# RocketDuino.net
KiCad netlist of a schematic drawn in EAGLE
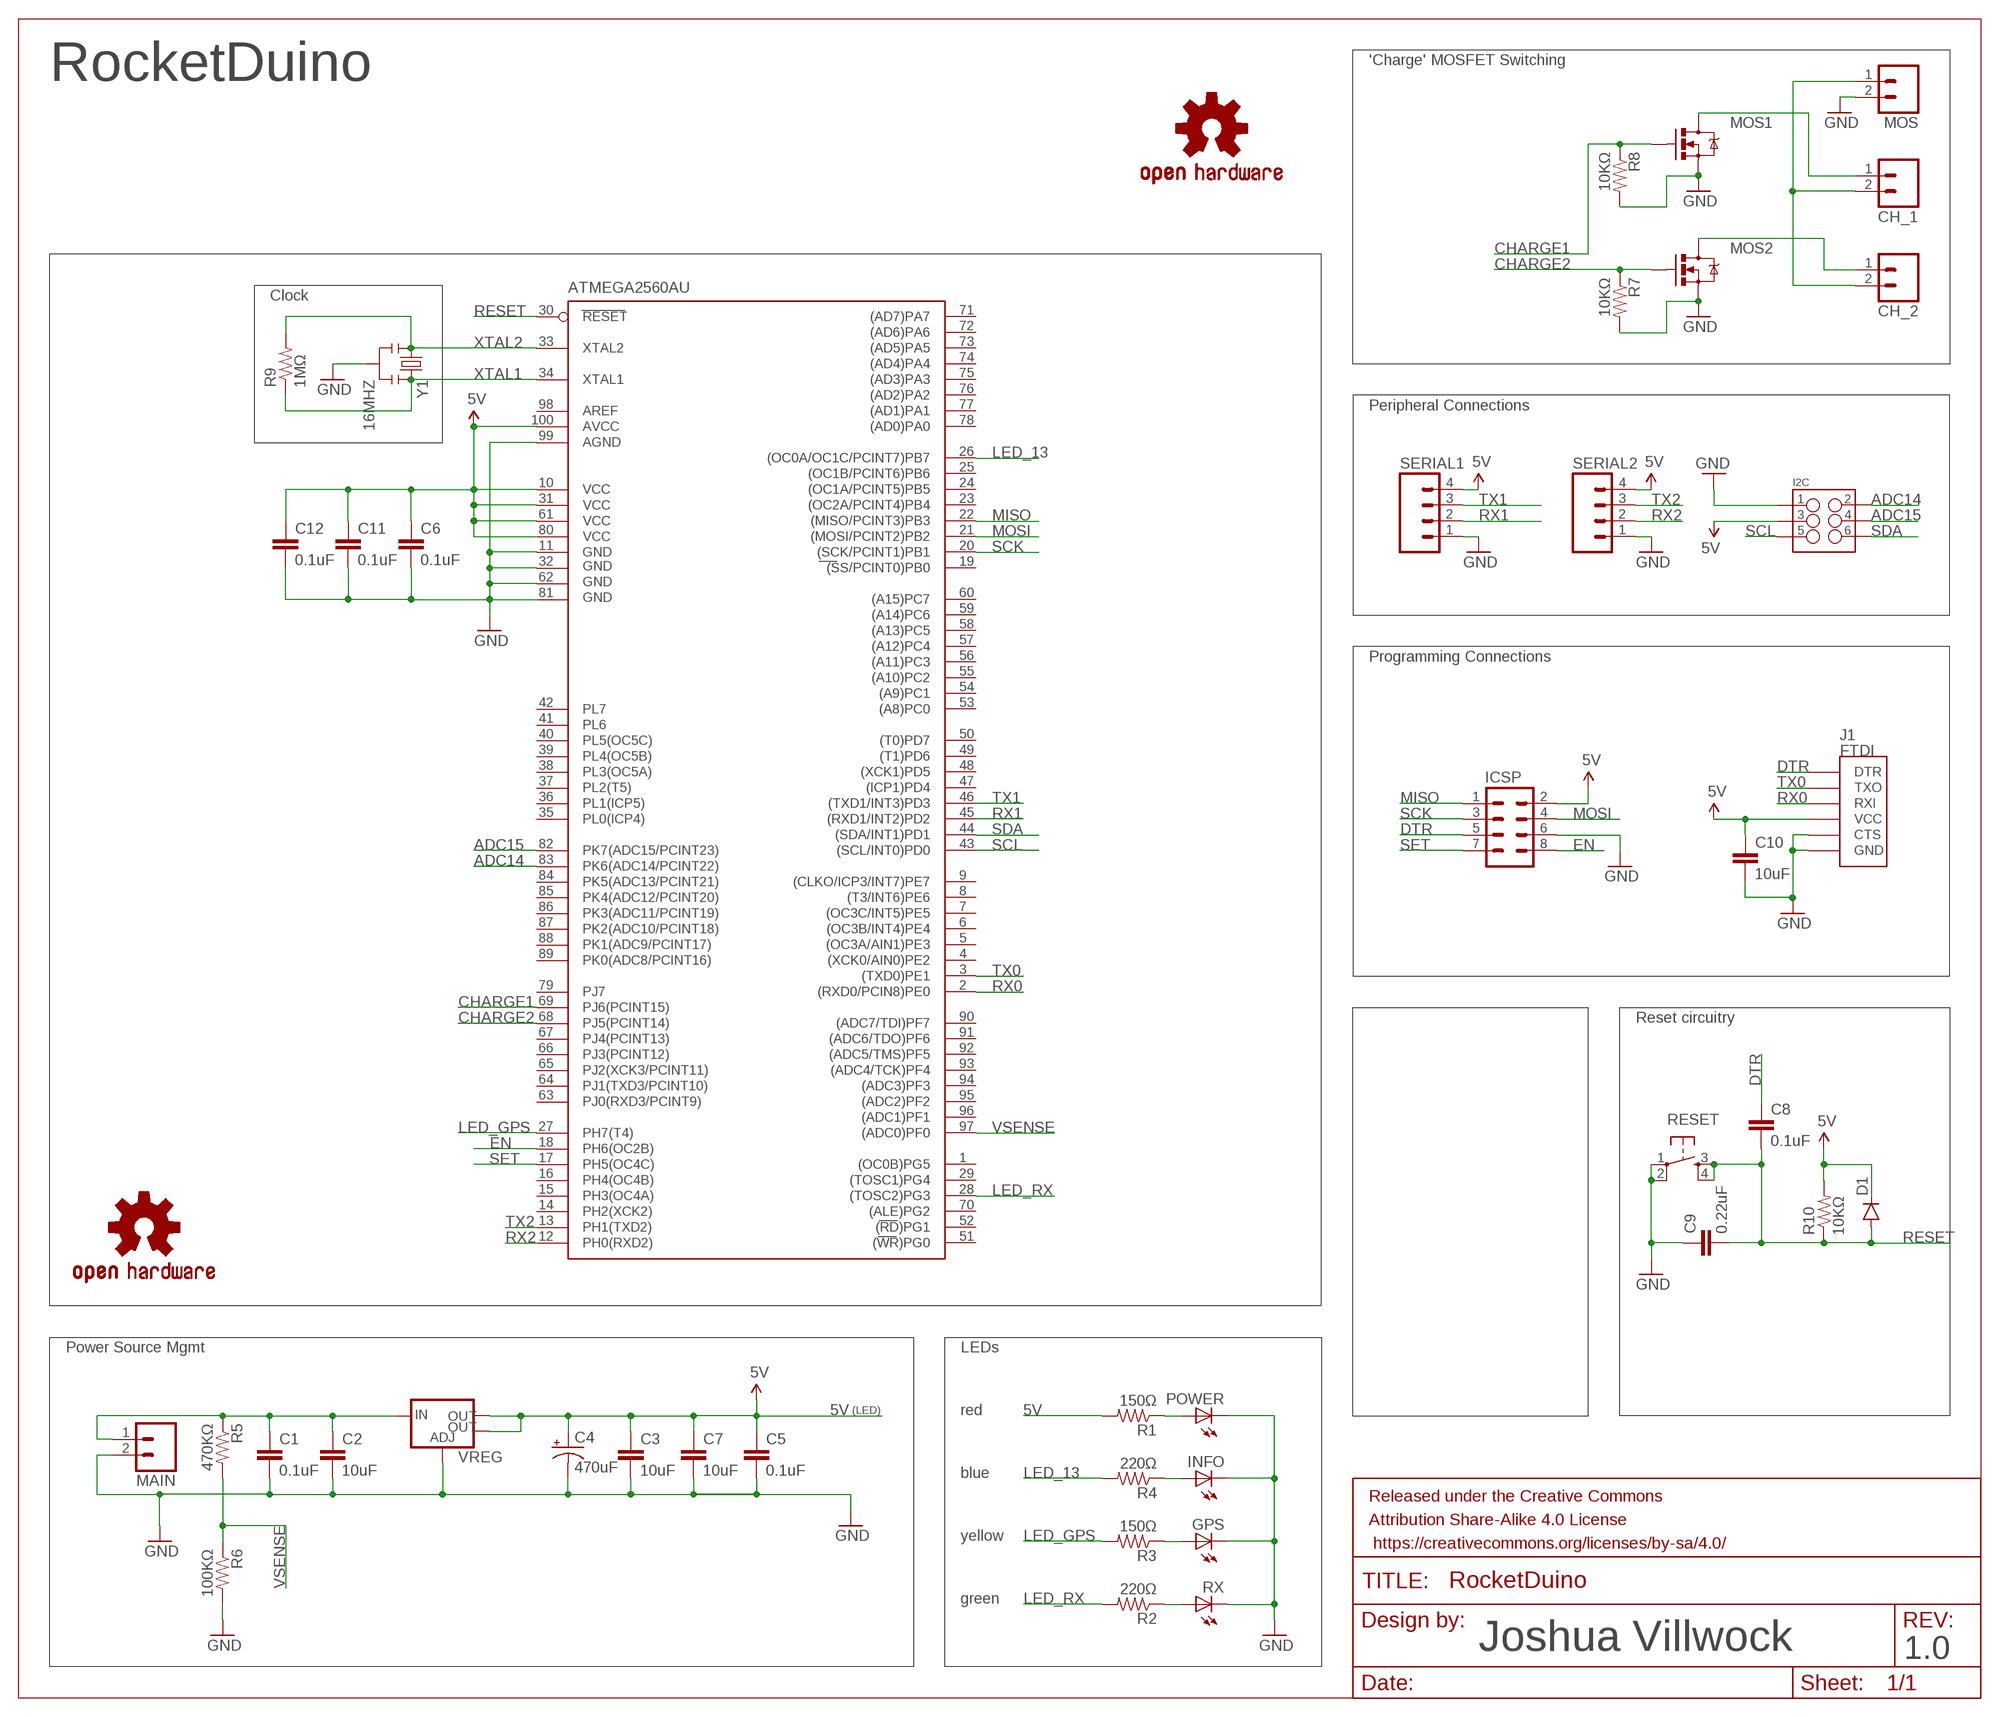
[diagram p0: schematic, sheet 1]

(export (version "E")
  (design (tool "Eeschema 10.0.6"))
  (components
    (comp (ref "ATMEGA2560AU")
      (value "ATMEGA2560AU")
      (footprint "eagle-import:TQFP100")
      (libsource (lib "eagle-import") (part "ATMEGA2560AU"))
    )
    (comp (ref "C1")
      (value "0.1uF")
      (footprint "eagle-import:1206")
      (libsource (lib "eagle-import") (part "CAP1206"))
    )
    (comp (ref "C2")
      (value "10uF")
      (footprint "eagle-import:1206")
      (libsource (lib "eagle-import") (part "CAP1206"))
    )
    (comp (ref "C3")
      (value "10uF")
      (footprint "eagle-import:1206")
      (libsource (lib "eagle-import") (part "CAP1206"))
    )
    (comp (ref "C4")
      (value "470uF")
      (footprint "eagle-import:CPOL-RADIAL-100UF-25V")
      (libsource (lib "eagle-import") (part "CAP_POLPTH1"))
    )
    (comp (ref "C5")
      (value "0.1uF")
      (footprint "eagle-import:1206")
      (libsource (lib "eagle-import") (part "CAP1206"))
    )
    (comp (ref "C6")
      (value "0.1uF")
      (footprint "eagle-import:1206")
      (libsource (lib "eagle-import") (part "CAP1206"))
    )
    (comp (ref "C7")
      (value "10uF")
      (footprint "eagle-import:1206")
      (libsource (lib "eagle-import") (part "CAP1206"))
    )
    (comp (ref "C8")
      (value "0.1uF")
      (footprint "eagle-import:1206")
      (libsource (lib "eagle-import") (part "CAP1206"))
    )
    (comp (ref "C9")
      (value "0.22uF")
      (footprint "eagle-import:1206")
      (libsource (lib "eagle-import") (part "CAP1206"))
    )
    (comp (ref "C10")
      (value "10uF")
      (footprint "eagle-import:1206")
      (libsource (lib "eagle-import") (part "CAP1206"))
    )
    (comp (ref "C11")
      (value "0.1uF")
      (footprint "eagle-import:1206")
      (libsource (lib "eagle-import") (part "CAP1206"))
    )
    (comp (ref "C12")
      (value "0.1uF")
      (footprint "eagle-import:1206")
      (libsource (lib "eagle-import") (part "CAP1206"))
    )
    (comp (ref "CH_1")
      (value "M02LOCK_LONGPADS")
      (footprint "eagle-import:1X02_LOCK_LONGPADS")
      (libsource (lib "eagle-import") (part "M02LOCK_LONGPADS"))
    )
    (comp (ref "CH_2")
      (value "M02LOCK_LONGPADS")
      (footprint "eagle-import:1X02_LOCK_LONGPADS")
      (libsource (lib "eagle-import") (part "M02LOCK_LONGPADS"))
    )
    (comp (ref "D1")
      (value "DIODESMA-ALT")
      (footprint "eagle-import:SMA-DIODE_ALT")
      (libsource (lib "eagle-import") (part "DIODESMA-ALT"))
    )
    (comp (ref "FRAME1")
      (value "FRAME-LEDGER")
      (footprint "eagle-import:CREATIVE_COMMONS")
      (libsource (lib "eagle-import") (part "FRAME-LEDGER"))
    )
    (comp (ref "GPS")
      (value "LEDSML0805")
      (footprint "eagle-import:SML0805")
      (libsource (lib "eagle-import") (part "LEDSML0805"))
    )
    (comp (ref "I2C")
      (value "M03X2FEMALE")
      (footprint "eagle-import:2X3")
      (libsource (lib "eagle-import") (part "M03X2FEMALE"))
    )
    (comp (ref "ICSP")
      (value "M04X2")
      (footprint "eagle-import:2X4")
      (libsource (lib "eagle-import") (part "M04X2"))
    )
    (comp (ref "INFO")
      (value "LEDSML0805")
      (footprint "eagle-import:SML0805")
      (libsource (lib "eagle-import") (part "LEDSML0805"))
    )
    (comp (ref "J1")
      (value "FTDI")
      (footprint "eagle-import:FTDI_DEVICE_SIDE")
      (libsource (lib "eagle-import") (part "FTDI_DEVICE"))
    )
    (comp (ref "LOGO1")
      (value "OSHW-LOGOM")
      (footprint "eagle-import:OSHW-LOGO-M")
      (libsource (lib "eagle-import") (part "OSHW-LOGOM"))
    )
    (comp (ref "LOGO2")
      (value "OSHW-LOGOM")
      (footprint "eagle-import:OSHW-LOGO-M")
      (libsource (lib "eagle-import") (part "OSHW-LOGOM"))
    )
    (comp (ref "MAIN")
      (value "M02LOCK_LONGPADS")
      (footprint "eagle-import:1X02_LOCK_LONGPADS")
      (libsource (lib "eagle-import") (part "M02LOCK_LONGPADS"))
    )
    (comp (ref "MOS")
      (value "M02LOCK_LONGPADS")
      (footprint "eagle-import:1X02_LOCK_LONGPADS")
      (libsource (lib "eagle-import") (part "M02LOCK_LONGPADS"))
    )
    (comp (ref "MOS1")
      (value "MOSFET-NCHANNELFQP30N06L")
      (footprint "eagle-import:TO220V")
      (libsource (lib "eagle-import") (part "MOSFET-NCHANNELFQP30N06L"))
    )
    (comp (ref "MOS2")
      (value "MOSFET-NCHANNELFQP30N06L")
      (footprint "eagle-import:TO220V")
      (libsource (lib "eagle-import") (part "MOSFET-NCHANNELFQP30N06L"))
    )
    (comp (ref "POWER")
      (value "LEDSML0805")
      (footprint "eagle-import:SML0805")
      (libsource (lib "eagle-import") (part "LEDSML0805"))
    )
    (comp (ref "R1")
      (value "150Ω")
      (footprint "eagle-import:1206")
      (libsource (lib "eagle-import") (part "RESISTOR1206"))
    )
    (comp (ref "R2")
      (value "220Ω")
      (footprint "eagle-import:1206")
      (libsource (lib "eagle-import") (part "RESISTOR1206"))
    )
    (comp (ref "R3")
      (value "150Ω")
      (footprint "eagle-import:1206")
      (libsource (lib "eagle-import") (part "RESISTOR1206"))
    )
    (comp (ref "R4")
      (value "220Ω")
      (footprint "eagle-import:1206")
      (libsource (lib "eagle-import") (part "RESISTOR1206"))
    )
    (comp (ref "R5")
      (value "470KΩ")
      (footprint "eagle-import:1206")
      (libsource (lib "eagle-import") (part "RESISTOR1206"))
    )
    (comp (ref "R6")
      (value "100KΩ")
      (footprint "eagle-import:1206")
      (libsource (lib "eagle-import") (part "RESISTOR1206"))
    )
    (comp (ref "R7")
      (value "10KΩ")
      (footprint "eagle-import:1206")
      (libsource (lib "eagle-import") (part "RESISTOR1206"))
    )
    (comp (ref "R8")
      (value "10KΩ")
      (footprint "eagle-import:1206")
      (libsource (lib "eagle-import") (part "RESISTOR1206"))
    )
    (comp (ref "R9")
      (value "1MΩ")
      (footprint "eagle-import:1206")
      (libsource (lib "eagle-import") (part "RESISTOR1206"))
    )
    (comp (ref "R10")
      (value "10KΩ")
      (footprint "eagle-import:1206")
      (libsource (lib "eagle-import") (part "RESISTOR1206"))
    )
    (comp (ref "RESET")
      (value "SWITCH_SPST_4_PINSQUARE")
      (footprint "eagle-import:TACTILE-SWITCH-SMD")
      (libsource (lib "eagle-import") (part "SWITCH_SPST_4_PINSQUARE"))
    )
    (comp (ref "RX")
      (value "LEDSML0805")
      (footprint "eagle-import:SML0805")
      (libsource (lib "eagle-import") (part "LEDSML0805"))
    )
    (comp (ref "SERIAL1")
      (value "M04POLAR")
      (footprint "eagle-import:MOLEX-1X4")
      (libsource (lib "eagle-import") (part "M04POLAR"))
    )
    (comp (ref "SERIAL2")
      (value "M04POLAR")
      (footprint "eagle-import:MOLEX-1X4")
      (libsource (lib "eagle-import") (part "M04POLAR"))
    )
    (comp (ref "VREG")
      (value "V_REG_LM1117SOT223")
      (footprint "eagle-import:SOT223")
      (libsource (lib "eagle-import") (part "V_REG_LM1117SOT223"))
    )
    (comp (ref "Y1")
      (value "16MHZ")
      (footprint "eagle-import:RESONATOR-SMD")
      (libsource (lib "eagle-import") (part "RESONATOR16MHZ"))
    )
  )
  (nets
    (net (code "1") (name "/ADC14") (class "Default")
      (node (ref "ATMEGA2560AU") (pin "83") (pinfunction "PK6(ADC14/PCINT22)_83") (pintype "bidirectional"))
      (node (ref "I2C") (pin "2") (pinfunction "2_2") (pintype "bidirectional"))
    )
    (net (code "2") (name "/ADC15") (class "Default")
      (node (ref "ATMEGA2560AU") (pin "82") (pinfunction "PK7(ADC15/PCINT23)_82") (pintype "bidirectional"))
      (node (ref "I2C") (pin "4") (pinfunction "4_4") (pintype "bidirectional"))
    )
    (net (code "3") (name "/CHARGE1") (class "Default")
      (node (ref "ATMEGA2560AU") (pin "69") (pinfunction "PJ6(PCINT15)_69") (pintype "bidirectional"))
      (node (ref "MOS1") (pin "1") (pinfunction "G_1") (pintype "passive"))
      (node (ref "R8") (pin "1") (pinfunction "1_1") (pintype "passive"))
    )
    (net (code "4") (name "/CHARGE2") (class "Default")
      (node (ref "ATMEGA2560AU") (pin "68") (pinfunction "PJ5(PCINT14)_68") (pintype "bidirectional"))
      (node (ref "MOS2") (pin "1") (pinfunction "G_1") (pintype "passive"))
      (node (ref "R7") (pin "1") (pinfunction "1_1") (pintype "passive"))
    )
    (net (code "5") (name "/DTR") (class "Default")
      (node (ref "C8") (pin "1") (pinfunction "1_1") (pintype "passive"))
      (node (ref "ICSP") (pin "5") (pinfunction "5_5") (pintype "passive"))
      (node (ref "J1") (pin "P$1") (pinfunction "DTR_P$1") (pintype "bidirectional"))
    )
    (net (code "6") (name "/EN") (class "Default")
      (node (ref "ATMEGA2560AU") (pin "18") (pinfunction "PH6(OC2B)_18") (pintype "bidirectional"))
      (node (ref "ICSP") (pin "8") (pinfunction "8_8") (pintype "passive"))
    )
    (net (code "7") (name "/LED_13") (class "Default")
      (node (ref "ATMEGA2560AU") (pin "26") (pinfunction "(OC0A/OC1C/PCINT7)PB7_26") (pintype "bidirectional"))
      (node (ref "R4") (pin "2") (pinfunction "2_2") (pintype "passive"))
    )
    (net (code "8") (name "/LED_GPS") (class "Default")
      (node (ref "ATMEGA2560AU") (pin "27") (pinfunction "PH7(T4)_27") (pintype "bidirectional"))
      (node (ref "R3") (pin "2") (pinfunction "2_2") (pintype "passive"))
    )
    (net (code "9") (name "/LED_RX") (class "Default")
      (node (ref "ATMEGA2560AU") (pin "28") (pinfunction "(TOSC2)PG3_28") (pintype "bidirectional"))
      (node (ref "R2") (pin "2") (pinfunction "2_2") (pintype "passive"))
    )
    (net (code "10") (name "/MISO") (class "Default")
      (node (ref "ATMEGA2560AU") (pin "22") (pinfunction "(MISO/PCINT3)PB3_22") (pintype "bidirectional"))
      (node (ref "ICSP") (pin "1") (pinfunction "1_1") (pintype "passive"))
    )
    (net (code "11") (name "/MOSI") (class "Default")
      (node (ref "ATMEGA2560AU") (pin "21") (pinfunction "(MOSI/PCINT2)PB2_21") (pintype "bidirectional"))
      (node (ref "ICSP") (pin "4") (pinfunction "4_4") (pintype "passive"))
    )
    (net (code "12") (name "/RESET") (class "Default")
      (node (ref "ATMEGA2560AU") (pin "30") (pinfunction "RESET_30") (pintype "input"))
      (node (ref "C8") (pin "2") (pinfunction "2_2") (pintype "passive"))
      (node (ref "C9") (pin "2") (pinfunction "2_2") (pintype "passive"))
      (node (ref "D1") (pin "A") (pinfunction "A_A") (pintype "passive"))
      (node (ref "R10") (pin "1") (pinfunction "1_1") (pintype "passive"))
      (node (ref "RESET") (pin "3") (pinfunction "3_3") (pintype "passive"))
      (node (ref "RESET") (pin "4") (pinfunction "4_4") (pintype "passive"))
    )
    (net (code "13") (name "/RX0") (class "Default")
      (node (ref "ATMEGA2560AU") (pin "2") (pinfunction "(RXD0/PCIN8)PE0_2") (pintype "bidirectional"))
      (node (ref "J1") (pin "P$3") (pinfunction "RXI_P$3") (pintype "bidirectional"))
    )
    (net (code "14") (name "/RX1") (class "Default")
      (node (ref "ATMEGA2560AU") (pin "45") (pinfunction "(RXD1/INT2)PD2_45") (pintype "bidirectional"))
      (node (ref "SERIAL1") (pin "2") (pinfunction "2_2") (pintype "passive"))
    )
    (net (code "15") (name "/RX2") (class "Default")
      (node (ref "ATMEGA2560AU") (pin "12") (pinfunction "PH0(RXD2)_12") (pintype "bidirectional"))
      (node (ref "SERIAL2") (pin "2") (pinfunction "2_2") (pintype "passive"))
    )
    (net (code "16") (name "/SCK") (class "Default")
      (node (ref "ATMEGA2560AU") (pin "20") (pinfunction "(SCK/PCINT1)PB1_20") (pintype "bidirectional"))
      (node (ref "ICSP") (pin "3") (pinfunction "3_3") (pintype "passive"))
    )
    (net (code "17") (name "/SCL") (class "Default")
      (node (ref "ATMEGA2560AU") (pin "43") (pinfunction "(SCL/INT0)PD0_43") (pintype "bidirectional"))
      (node (ref "I2C") (pin "5") (pinfunction "5_5") (pintype "bidirectional"))
    )
    (net (code "18") (name "/SDA") (class "Default")
      (node (ref "ATMEGA2560AU") (pin "44") (pinfunction "(SDA/INT1)PD1_44") (pintype "bidirectional"))
      (node (ref "I2C") (pin "6") (pinfunction "6_6") (pintype "bidirectional"))
    )
    (net (code "19") (name "/SET") (class "Default")
      (node (ref "ATMEGA2560AU") (pin "17") (pinfunction "PH5(OC4C)_17") (pintype "bidirectional"))
      (node (ref "ICSP") (pin "7") (pinfunction "7_7") (pintype "passive"))
    )
    (net (code "20") (name "/TX0") (class "Default")
      (node (ref "ATMEGA2560AU") (pin "3") (pinfunction "(TXD0)PE1_3") (pintype "bidirectional"))
      (node (ref "J1") (pin "P$2") (pinfunction "TXO_P$2") (pintype "bidirectional"))
    )
    (net (code "21") (name "/TX1") (class "Default")
      (node (ref "ATMEGA2560AU") (pin "46") (pinfunction "(TXD1/INT3)PD3_46") (pintype "bidirectional"))
      (node (ref "SERIAL1") (pin "3") (pinfunction "3_3") (pintype "passive"))
    )
    (net (code "22") (name "/TX2") (class "Default")
      (node (ref "ATMEGA2560AU") (pin "13") (pinfunction "PH1(TXD2)_13") (pintype "bidirectional"))
      (node (ref "SERIAL2") (pin "3") (pinfunction "3_3") (pintype "passive"))
    )
    (net (code "23") (name "/VSENSE") (class "Default")
      (node (ref "ATMEGA2560AU") (pin "97") (pinfunction "(ADC0)PF0_97") (pintype "bidirectional"))
      (node (ref "R5") (pin "2") (pinfunction "2_2") (pintype "passive"))
      (node (ref "R6") (pin "1") (pinfunction "1_1") (pintype "passive"))
    )
    (net (code "24") (name "/XTAL1") (class "Default")
      (node (ref "ATMEGA2560AU") (pin "34") (pinfunction "XTAL1_34") (pintype "input"))
      (node (ref "R9") (pin "1") (pinfunction "1_1") (pintype "passive"))
      (node (ref "Y1") (pin "3") (pinfunction "3_3") (pintype "passive"))
    )
    (net (code "25") (name "/XTAL2") (class "Default")
      (node (ref "ATMEGA2560AU") (pin "33") (pinfunction "XTAL2_33") (pintype "output"))
      (node (ref "R9") (pin "2") (pinfunction "2_2") (pintype "passive"))
      (node (ref "Y1") (pin "1") (pinfunction "1_1") (pintype "passive"))
    )
    (net (code "26") (name "5V") (class "Default")
      (node (ref "ATMEGA2560AU") (pin "10") (pinfunction "VCC_10") (pintype "power_in"))
      (node (ref "ATMEGA2560AU") (pin "100") (pinfunction "AVCC_100") (pintype "power_in"))
      (node (ref "ATMEGA2560AU") (pin "31") (pinfunction "VCC1_31") (pintype "power_in"))
      (node (ref "ATMEGA2560AU") (pin "61") (pinfunction "VCC2_61") (pintype "power_in"))
      (node (ref "ATMEGA2560AU") (pin "80") (pinfunction "VCC3_80") (pintype "power_in"))
      (node (ref "C10") (pin "1") (pinfunction "1_1") (pintype "passive"))
      (node (ref "C11") (pin "1") (pinfunction "1_1") (pintype "passive"))
      (node (ref "C12") (pin "1") (pinfunction "1_1") (pintype "passive"))
      (node (ref "C3") (pin "1") (pinfunction "1_1") (pintype "passive"))
      (node (ref "C4") (pin "1") (pinfunction "+_1") (pintype "passive"))
      (node (ref "C5") (pin "1") (pinfunction "1_1") (pintype "passive"))
      (node (ref "C6") (pin "1") (pinfunction "1_1") (pintype "passive"))
      (node (ref "C7") (pin "1") (pinfunction "1_1") (pintype "passive"))
      (node (ref "D1") (pin "C") (pinfunction "C_C") (pintype "passive"))
      (node (ref "I2C") (pin "3") (pinfunction "3_3") (pintype "bidirectional"))
      (node (ref "ICSP") (pin "2") (pinfunction "2_2") (pintype "passive"))
      (node (ref "J1") (pin "P$4") (pinfunction "VCC_P$4") (pintype "bidirectional"))
      (node (ref "R1") (pin "2") (pinfunction "2_2") (pintype "passive"))
      (node (ref "R10") (pin "2") (pinfunction "2_2") (pintype "passive"))
      (node (ref "SERIAL1") (pin "4") (pinfunction "4_4") (pintype "passive"))
      (node (ref "SERIAL2") (pin "4") (pinfunction "4_4") (pintype "passive"))
      (node (ref "VREG") (pin "2") (pinfunction "OUT_2") (pintype "output"))
      (node (ref "VREG") (pin "4") (pinfunction "OUT_4") (pintype "output"))
    )
    (net (code "27") (name "GND") (class "Default")
      (node (ref "ATMEGA2560AU") (pin "11") (pinfunction "GND_11") (pintype "power_in"))
      (node (ref "ATMEGA2560AU") (pin "32") (pinfunction "GND1_32") (pintype "power_in"))
      (node (ref "ATMEGA2560AU") (pin "62") (pinfunction "GND2_62") (pintype "power_in"))
      (node (ref "ATMEGA2560AU") (pin "81") (pinfunction "GND3_81") (pintype "power_in"))
      (node (ref "ATMEGA2560AU") (pin "99") (pinfunction "AGND_99") (pintype "power_in"))
      (node (ref "C1") (pin "2") (pinfunction "2_2") (pintype "passive"))
      (node (ref "C10") (pin "2") (pinfunction "2_2") (pintype "passive"))
      (node (ref "C11") (pin "2") (pinfunction "2_2") (pintype "passive"))
      (node (ref "C12") (pin "2") (pinfunction "2_2") (pintype "passive"))
      (node (ref "C2") (pin "2") (pinfunction "2_2") (pintype "passive"))
      (node (ref "C3") (pin "2") (pinfunction "2_2") (pintype "passive"))
      (node (ref "C4") (pin "2") (pinfunction "-_2") (pintype "passive"))
      (node (ref "C5") (pin "2") (pinfunction "2_2") (pintype "passive"))
      (node (ref "C6") (pin "2") (pinfunction "2_2") (pintype "passive"))
      (node (ref "C7") (pin "2") (pinfunction "2_2") (pintype "passive"))
      (node (ref "C9") (pin "1") (pinfunction "1_1") (pintype "passive"))
      (node (ref "GPS") (pin "C") (pinfunction "C_C") (pintype "passive"))
      (node (ref "I2C") (pin "1") (pinfunction "1_1") (pintype "bidirectional"))
      (node (ref "ICSP") (pin "6") (pinfunction "6_6") (pintype "passive"))
      (node (ref "INFO") (pin "C") (pinfunction "C_C") (pintype "passive"))
      (node (ref "J1") (pin "P$5") (pinfunction "CTS_P$5") (pintype "bidirectional"))
      (node (ref "J1") (pin "P$6") (pinfunction "GND_P$6") (pintype "bidirectional"))
      (node (ref "MAIN") (pin "2") (pinfunction "2_2") (pintype "passive"))
      (node (ref "MOS") (pin "2") (pinfunction "2_2") (pintype "passive"))
      (node (ref "MOS1") (pin "3") (pinfunction "S_3") (pintype "passive"))
      (node (ref "MOS2") (pin "3") (pinfunction "S_3") (pintype "passive"))
      (node (ref "POWER") (pin "C") (pinfunction "C_C") (pintype "passive"))
      (node (ref "R6") (pin "2") (pinfunction "2_2") (pintype "passive"))
      (node (ref "R7") (pin "2") (pinfunction "2_2") (pintype "passive"))
      (node (ref "R8") (pin "2") (pinfunction "2_2") (pintype "passive"))
      (node (ref "RESET") (pin "1") (pinfunction "1_1") (pintype "passive"))
      (node (ref "RESET") (pin "2") (pinfunction "2_2") (pintype "passive"))
      (node (ref "RX") (pin "C") (pinfunction "C_C") (pintype "passive"))
      (node (ref "SERIAL1") (pin "1") (pinfunction "1_1") (pintype "passive"))
      (node (ref "SERIAL2") (pin "1") (pinfunction "1_1") (pintype "passive"))
      (node (ref "VREG") (pin "1") (pinfunction "ADJ_1") (pintype "input"))
      (node (ref "Y1") (pin "2") (pinfunction "2_2") (pintype "passive"))
    )
    (net (code "28") (name "Net-(CH_1-Pad2)") (class "Default")
      (node (ref "CH_1") (pin "2") (pinfunction "2_2") (pintype "passive"))
      (node (ref "CH_2") (pin "2") (pinfunction "2_2") (pintype "passive"))
      (node (ref "MOS") (pin "1") (pinfunction "1_1") (pintype "passive"))
    )
    (net (code "29") (name "Net-(GPS-PadA)") (class "Default")
      (node (ref "GPS") (pin "A") (pinfunction "A_A") (pintype "passive"))
      (node (ref "R3") (pin "1") (pinfunction "1_1") (pintype "passive"))
    )
    (net (code "30") (name "Net-(INFO-PadA)") (class "Default")
      (node (ref "INFO") (pin "A") (pinfunction "A_A") (pintype "passive"))
      (node (ref "R4") (pin "1") (pinfunction "1_1") (pintype "passive"))
    )
    (net (code "31") (name "Net-(MOS1-D)") (class "Default")
      (node (ref "CH_1") (pin "1") (pinfunction "1_1") (pintype "passive"))
      (node (ref "MOS1") (pin "2") (pinfunction "D_2") (pintype "passive"))
    )
    (net (code "32") (name "Net-(MOS2-D)") (class "Default")
      (node (ref "CH_2") (pin "1") (pinfunction "1_1") (pintype "passive"))
      (node (ref "MOS2") (pin "2") (pinfunction "D_2") (pintype "passive"))
    )
    (net (code "33") (name "Net-(POWER-PadA)") (class "Default")
      (node (ref "POWER") (pin "A") (pinfunction "A_A") (pintype "passive"))
      (node (ref "R1") (pin "1") (pinfunction "1_1") (pintype "passive"))
    )
    (net (code "34") (name "Net-(R2-Pad1)") (class "Default")
      (node (ref "R2") (pin "1") (pinfunction "1_1") (pintype "passive"))
      (node (ref "RX") (pin "A") (pinfunction "A_A") (pintype "passive"))
    )
    (net (code "35") (name "Net-(VREG-IN)") (class "Default")
      (node (ref "C1") (pin "1") (pinfunction "1_1") (pintype "passive"))
      (node (ref "C2") (pin "1") (pinfunction "1_1") (pintype "passive"))
      (node (ref "MAIN") (pin "1") (pinfunction "1_1") (pintype "passive"))
      (node (ref "R5") (pin "1") (pinfunction "1_1") (pintype "passive"))
      (node (ref "VREG") (pin "3") (pinfunction "IN_3") (pintype "input"))
    )
    (net (code "36") (name "unconnected-(ATMEGA2560AU-(A8)PC0-Pad53)") (class "Default")
      (node (ref "ATMEGA2560AU") (pin "53") (pinfunction "(A8)PC0_53") (pintype "bidirectional"))
    )
    (net (code "37") (name "unconnected-(ATMEGA2560AU-(A9)PC1-Pad54)") (class "Default")
      (node (ref "ATMEGA2560AU") (pin "54") (pinfunction "(A9)PC1_54") (pintype "bidirectional"))
    )
    (net (code "38") (name "unconnected-(ATMEGA2560AU-(A10)PC2-Pad55)") (class "Default")
      (node (ref "ATMEGA2560AU") (pin "55") (pinfunction "(A10)PC2_55") (pintype "bidirectional"))
    )
    (net (code "39") (name "unconnected-(ATMEGA2560AU-(A11)PC3-Pad56)") (class "Default")
      (node (ref "ATMEGA2560AU") (pin "56") (pinfunction "(A11)PC3_56") (pintype "bidirectional"))
    )
    (net (code "40") (name "unconnected-(ATMEGA2560AU-(A12)PC4-Pad57)") (class "Default")
      (node (ref "ATMEGA2560AU") (pin "57") (pinfunction "(A12)PC4_57") (pintype "bidirectional"))
    )
    (net (code "41") (name "unconnected-(ATMEGA2560AU-(A13)PC5-Pad58)") (class "Default")
      (node (ref "ATMEGA2560AU") (pin "58") (pinfunction "(A13)PC5_58") (pintype "bidirectional"))
    )
    (net (code "42") (name "unconnected-(ATMEGA2560AU-(A14)PC6-Pad59)") (class "Default")
      (node (ref "ATMEGA2560AU") (pin "59") (pinfunction "(A14)PC6_59") (pintype "bidirectional"))
    )
    (net (code "43") (name "unconnected-(ATMEGA2560AU-(A15)PC7-Pad60)") (class "Default")
      (node (ref "ATMEGA2560AU") (pin "60") (pinfunction "(A15)PC7_60") (pintype "bidirectional"))
    )
    (net (code "44") (name "unconnected-(ATMEGA2560AU-(AD0)PA0-Pad78)") (class "Default")
      (node (ref "ATMEGA2560AU") (pin "78") (pinfunction "(AD0)PA0_78") (pintype "bidirectional"))
    )
    (net (code "45") (name "unconnected-(ATMEGA2560AU-(AD1)PA1-Pad77)") (class "Default")
      (node (ref "ATMEGA2560AU") (pin "77") (pinfunction "(AD1)PA1_77") (pintype "bidirectional"))
    )
    (net (code "46") (name "unconnected-(ATMEGA2560AU-(AD2)PA2-Pad76)") (class "Default")
      (node (ref "ATMEGA2560AU") (pin "76") (pinfunction "(AD2)PA2_76") (pintype "bidirectional"))
    )
    (net (code "47") (name "unconnected-(ATMEGA2560AU-(AD3)PA3-Pad75)") (class "Default")
      (node (ref "ATMEGA2560AU") (pin "75") (pinfunction "(AD3)PA3_75") (pintype "bidirectional"))
    )
    (net (code "48") (name "unconnected-(ATMEGA2560AU-(AD4)PA4-Pad74)") (class "Default")
      (node (ref "ATMEGA2560AU") (pin "74") (pinfunction "(AD4)PA4_74") (pintype "bidirectional"))
    )
    (net (code "49") (name "unconnected-(ATMEGA2560AU-(AD5)PA5-Pad73)") (class "Default")
      (node (ref "ATMEGA2560AU") (pin "73") (pinfunction "(AD5)PA5_73") (pintype "bidirectional"))
    )
    (net (code "50") (name "unconnected-(ATMEGA2560AU-(AD6)PA6-Pad72)") (class "Default")
      (node (ref "ATMEGA2560AU") (pin "72") (pinfunction "(AD6)PA6_72") (pintype "bidirectional"))
    )
    (net (code "51") (name "unconnected-(ATMEGA2560AU-(AD7)PA7-Pad71)") (class "Default")
      (node (ref "ATMEGA2560AU") (pin "71") (pinfunction "(AD7)PA7_71") (pintype "bidirectional"))
    )
    (net (code "52") (name "unconnected-(ATMEGA2560AU-(ADC1)PF1-Pad96)") (class "Default")
      (node (ref "ATMEGA2560AU") (pin "96") (pinfunction "(ADC1)PF1_96") (pintype "bidirectional"))
    )
    (net (code "53") (name "unconnected-(ATMEGA2560AU-(ADC2)PF2-Pad95)") (class "Default")
      (node (ref "ATMEGA2560AU") (pin "95") (pinfunction "(ADC2)PF2_95") (pintype "bidirectional"))
    )
    (net (code "54") (name "unconnected-(ATMEGA2560AU-(ADC3)PF3-Pad94)") (class "Default")
      (node (ref "ATMEGA2560AU") (pin "94") (pinfunction "(ADC3)PF3_94") (pintype "bidirectional"))
    )
    (net (code "55") (name "unconnected-(ATMEGA2560AU-(ADC4{slash}TCK)PF4-Pad93)") (class "Default")
      (node (ref "ATMEGA2560AU") (pin "93") (pinfunction "(ADC4/TCK)PF4_93") (pintype "bidirectional"))
    )
    (net (code "56") (name "unconnected-(ATMEGA2560AU-(ADC5{slash}TMS)PF5-Pad92)") (class "Default")
      (node (ref "ATMEGA2560AU") (pin "92") (pinfunction "(ADC5/TMS)PF5_92") (pintype "bidirectional"))
    )
    (net (code "57") (name "unconnected-(ATMEGA2560AU-(ADC6{slash}TDO)PF6-Pad91)") (class "Default")
      (node (ref "ATMEGA2560AU") (pin "91") (pinfunction "(ADC6/TDO)PF6_91") (pintype "bidirectional"))
    )
    (net (code "58") (name "unconnected-(ATMEGA2560AU-(ADC7{slash}TDI)PF7-Pad90)") (class "Default")
      (node (ref "ATMEGA2560AU") (pin "90") (pinfunction "(ADC7/TDI)PF7_90") (pintype "bidirectional"))
    )
    (net (code "59") (name "unconnected-(ATMEGA2560AU-(ALE)PG2-Pad70)") (class "Default")
      (node (ref "ATMEGA2560AU") (pin "70") (pinfunction "(ALE)PG2_70") (pintype "bidirectional"))
    )
    (net (code "60") (name "unconnected-(ATMEGA2560AU-(CLKO{slash}ICP3{slash}INT7)PE7-Pad9)") (class "Default")
      (node (ref "ATMEGA2560AU") (pin "9") (pinfunction "(CLKO/ICP3/INT7)PE7_9") (pintype "bidirectional"))
    )
    (net (code "61") (name "unconnected-(ATMEGA2560AU-(ICP1)PD4-Pad47)") (class "Default")
      (node (ref "ATMEGA2560AU") (pin "47") (pinfunction "(ICP1)PD4_47") (pintype "bidirectional"))
    )
    (net (code "62") (name "unconnected-(ATMEGA2560AU-(OC0B)PG5-Pad1)") (class "Default")
      (node (ref "ATMEGA2560AU") (pin "1") (pinfunction "(OC0B)PG5_1") (pintype "bidirectional"))
    )
    (net (code "63") (name "unconnected-(ATMEGA2560AU-(OC1A{slash}PCINT5)PB5-Pad24)") (class "Default")
      (node (ref "ATMEGA2560AU") (pin "24") (pinfunction "(OC1A/PCINT5)PB5_24") (pintype "bidirectional"))
    )
    (net (code "64") (name "unconnected-(ATMEGA2560AU-(OC1B{slash}PCINT6)PB6-Pad25)") (class "Default")
      (node (ref "ATMEGA2560AU") (pin "25") (pinfunction "(OC1B/PCINT6)PB6_25") (pintype "bidirectional"))
    )
    (net (code "65") (name "unconnected-(ATMEGA2560AU-(OC2A{slash}PCINT4)PB4-Pad23)") (class "Default")
      (node (ref "ATMEGA2560AU") (pin "23") (pinfunction "(OC2A/PCINT4)PB4_23") (pintype "bidirectional"))
    )
    (net (code "66") (name "unconnected-(ATMEGA2560AU-(OC3A{slash}AIN1)PE3-Pad5)") (class "Default")
      (node (ref "ATMEGA2560AU") (pin "5") (pinfunction "(OC3A/AIN1)PE3_5") (pintype "bidirectional"))
    )
    (net (code "67") (name "unconnected-(ATMEGA2560AU-(OC3B{slash}INT4)PE4-Pad6)") (class "Default")
      (node (ref "ATMEGA2560AU") (pin "6") (pinfunction "(OC3B/INT4)PE4_6") (pintype "bidirectional"))
    )
    (net (code "68") (name "unconnected-(ATMEGA2560AU-(OC3C{slash}INT5)PE5-Pad7)") (class "Default")
      (node (ref "ATMEGA2560AU") (pin "7") (pinfunction "(OC3C/INT5)PE5_7") (pintype "bidirectional"))
    )
    (net (code "69") (name "unconnected-(ATMEGA2560AU-(RD)PG1-Pad52)") (class "Default")
      (node (ref "ATMEGA2560AU") (pin "52") (pinfunction "(RD)PG1_52") (pintype "bidirectional"))
    )
    (net (code "70") (name "unconnected-(ATMEGA2560AU-(SS{slash}PCINT0)PB0-Pad19)") (class "Default")
      (node (ref "ATMEGA2560AU") (pin "19") (pinfunction "(SS/PCINT0)PB0_19") (pintype "bidirectional"))
    )
    (net (code "71") (name "unconnected-(ATMEGA2560AU-(T0)PD7-Pad50)") (class "Default")
      (node (ref "ATMEGA2560AU") (pin "50") (pinfunction "(T0)PD7_50") (pintype "bidirectional"))
    )
    (net (code "72") (name "unconnected-(ATMEGA2560AU-(T1)PD6-Pad49)") (class "Default")
      (node (ref "ATMEGA2560AU") (pin "49") (pinfunction "(T1)PD6_49") (pintype "bidirectional"))
    )
    (net (code "73") (name "unconnected-(ATMEGA2560AU-(T3{slash}INT6)PE6-Pad8)") (class "Default")
      (node (ref "ATMEGA2560AU") (pin "8") (pinfunction "(T3/INT6)PE6_8") (pintype "bidirectional"))
    )
    (net (code "74") (name "unconnected-(ATMEGA2560AU-(TOSC1)PG4-Pad29)") (class "Default")
      (node (ref "ATMEGA2560AU") (pin "29") (pinfunction "(TOSC1)PG4_29") (pintype "bidirectional"))
    )
    (net (code "75") (name "unconnected-(ATMEGA2560AU-(WR)PG0-Pad51)") (class "Default")
      (node (ref "ATMEGA2560AU") (pin "51") (pinfunction "(WR)PG0_51") (pintype "bidirectional"))
    )
    (net (code "76") (name "unconnected-(ATMEGA2560AU-(XCK0{slash}AIN0)PE2-Pad4)") (class "Default")
      (node (ref "ATMEGA2560AU") (pin "4") (pinfunction "(XCK0/AIN0)PE2_4") (pintype "bidirectional"))
    )
    (net (code "77") (name "unconnected-(ATMEGA2560AU-(XCK1)PD5-Pad48)") (class "Default")
      (node (ref "ATMEGA2560AU") (pin "48") (pinfunction "(XCK1)PD5_48") (pintype "bidirectional"))
    )
    (net (code "78") (name "unconnected-(ATMEGA2560AU-AREF-Pad98)") (class "Default")
      (node (ref "ATMEGA2560AU") (pin "98") (pinfunction "AREF_98") (pintype "bidirectional"))
    )
    (net (code "79") (name "unconnected-(ATMEGA2560AU-PH2(XCK2)-Pad14)") (class "Default")
      (node (ref "ATMEGA2560AU") (pin "14") (pinfunction "PH2(XCK2)_14") (pintype "bidirectional"))
    )
    (net (code "80") (name "unconnected-(ATMEGA2560AU-PH3(OC4A)-Pad15)") (class "Default")
      (node (ref "ATMEGA2560AU") (pin "15") (pinfunction "PH3(OC4A)_15") (pintype "bidirectional"))
    )
    (net (code "81") (name "unconnected-(ATMEGA2560AU-PH4(OC4B)-Pad16)") (class "Default")
      (node (ref "ATMEGA2560AU") (pin "16") (pinfunction "PH4(OC4B)_16") (pintype "bidirectional"))
    )
    (net (code "82") (name "unconnected-(ATMEGA2560AU-PJ0(RXD3{slash}PCINT9)-Pad63)") (class "Default")
      (node (ref "ATMEGA2560AU") (pin "63") (pinfunction "PJ0(RXD3/PCINT9)_63") (pintype "bidirectional"))
    )
    (net (code "83") (name "unconnected-(ATMEGA2560AU-PJ1(TXD3{slash}PCINT10)-Pad64)") (class "Default")
      (node (ref "ATMEGA2560AU") (pin "64") (pinfunction "PJ1(TXD3/PCINT10)_64") (pintype "bidirectional"))
    )
    (net (code "84") (name "unconnected-(ATMEGA2560AU-PJ2(XCK3{slash}PCINT11)-Pad65)") (class "Default")
      (node (ref "ATMEGA2560AU") (pin "65") (pinfunction "PJ2(XCK3/PCINT11)_65") (pintype "bidirectional"))
    )
    (net (code "85") (name "unconnected-(ATMEGA2560AU-PJ3(PCINT12)-Pad66)") (class "Default")
      (node (ref "ATMEGA2560AU") (pin "66") (pinfunction "PJ3(PCINT12)_66") (pintype "bidirectional"))
    )
    (net (code "86") (name "unconnected-(ATMEGA2560AU-PJ4(PCINT13)-Pad67)") (class "Default")
      (node (ref "ATMEGA2560AU") (pin "67") (pinfunction "PJ4(PCINT13)_67") (pintype "bidirectional"))
    )
    (net (code "87") (name "unconnected-(ATMEGA2560AU-PJ7-Pad79)") (class "Default")
      (node (ref "ATMEGA2560AU") (pin "79") (pinfunction "PJ7_79") (pintype "bidirectional"))
    )
    (net (code "88") (name "unconnected-(ATMEGA2560AU-PK0(ADC8{slash}PCINT16)-Pad89)") (class "Default")
      (node (ref "ATMEGA2560AU") (pin "89") (pinfunction "PK0(ADC8/PCINT16)_89") (pintype "bidirectional"))
    )
    (net (code "89") (name "unconnected-(ATMEGA2560AU-PK1(ADC9{slash}PCINT17)-Pad88)") (class "Default")
      (node (ref "ATMEGA2560AU") (pin "88") (pinfunction "PK1(ADC9/PCINT17)_88") (pintype "bidirectional"))
    )
    (net (code "90") (name "unconnected-(ATMEGA2560AU-PK2(ADC10{slash}PCINT18)-Pad87)") (class "Default")
      (node (ref "ATMEGA2560AU") (pin "87") (pinfunction "PK2(ADC10/PCINT18)_87") (pintype "bidirectional"))
    )
    (net (code "91") (name "unconnected-(ATMEGA2560AU-PK3(ADC11{slash}PCINT19)-Pad86)") (class "Default")
      (node (ref "ATMEGA2560AU") (pin "86") (pinfunction "PK3(ADC11/PCINT19)_86") (pintype "bidirectional"))
    )
    (net (code "92") (name "unconnected-(ATMEGA2560AU-PK4(ADC12{slash}PCINT20)-Pad85)") (class "Default")
      (node (ref "ATMEGA2560AU") (pin "85") (pinfunction "PK4(ADC12/PCINT20)_85") (pintype "bidirectional"))
    )
    (net (code "93") (name "unconnected-(ATMEGA2560AU-PK5(ADC13{slash}PCINT21)-Pad84)") (class "Default")
      (node (ref "ATMEGA2560AU") (pin "84") (pinfunction "PK5(ADC13/PCINT21)_84") (pintype "bidirectional"))
    )
    (net (code "94") (name "unconnected-(ATMEGA2560AU-PL0(ICP4)-Pad35)") (class "Default")
      (node (ref "ATMEGA2560AU") (pin "35") (pinfunction "PL0(ICP4)_35") (pintype "bidirectional"))
    )
    (net (code "95") (name "unconnected-(ATMEGA2560AU-PL1(ICP5)-Pad36)") (class "Default")
      (node (ref "ATMEGA2560AU") (pin "36") (pinfunction "PL1(ICP5)_36") (pintype "bidirectional"))
    )
    (net (code "96") (name "unconnected-(ATMEGA2560AU-PL2(T5)-Pad37)") (class "Default")
      (node (ref "ATMEGA2560AU") (pin "37") (pinfunction "PL2(T5)_37") (pintype "bidirectional"))
    )
    (net (code "97") (name "unconnected-(ATMEGA2560AU-PL3(OC5A)-Pad38)") (class "Default")
      (node (ref "ATMEGA2560AU") (pin "38") (pinfunction "PL3(OC5A)_38") (pintype "bidirectional"))
    )
    (net (code "98") (name "unconnected-(ATMEGA2560AU-PL4(OC5B)-Pad39)") (class "Default")
      (node (ref "ATMEGA2560AU") (pin "39") (pinfunction "PL4(OC5B)_39") (pintype "bidirectional"))
    )
    (net (code "99") (name "unconnected-(ATMEGA2560AU-PL5(OC5C)-Pad40)") (class "Default")
      (node (ref "ATMEGA2560AU") (pin "40") (pinfunction "PL5(OC5C)_40") (pintype "bidirectional"))
    )
    (net (code "100") (name "unconnected-(ATMEGA2560AU-PL6-Pad41)") (class "Default")
      (node (ref "ATMEGA2560AU") (pin "41") (pinfunction "PL6_41") (pintype "bidirectional"))
    )
    (net (code "101") (name "unconnected-(ATMEGA2560AU-PL7-Pad42)") (class "Default")
      (node (ref "ATMEGA2560AU") (pin "42") (pinfunction "PL7_42") (pintype "bidirectional"))
    )
  )
)
